# TranslationDir8Chan.net
KiCad netlist of a schematic drawn in Altium Designer
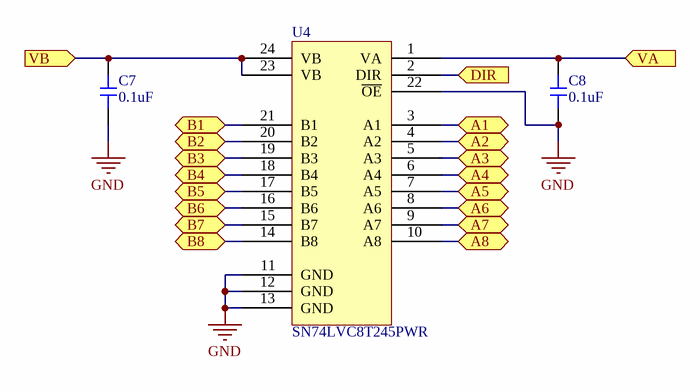
[diagram p0: TranslationDir8Chan.SchDoc]

(export (version "E")
  (design (tool "Eeschema 10.0.6"))
  (components
    (comp (ref "C7")
      (value "0.1uF")
      (footprint "AMDC:0603-CAP")
      (description "Capacitor")
      (libsource (lib "AMDC") (part "Capacitor"))
    )
    (comp (ref "C8")
      (value "0.1uF")
      (footprint "AMDC:0603-CAP")
      (description "Capacitor")
      (libsource (lib "AMDC") (part "Capacitor"))
    )
    (comp (ref "U4")
      (value "SN74LVC8T245PWR")
      (footprint "AMDC:TSOP65P640X120-24N")
      (description "IC BUS TRANSCVR 8BIT 24TSSOP")
      (libsource (lib "AMDC") (part "SN74LVC8T245PWR"))
    )
  )
  (nets
    (net (code "1") (name "/A1") (class "Default")
      (node (ref "U4") (pin "3") (pinfunction "A1_3") (pintype "passive"))
    )
    (net (code "2") (name "/A2") (class "Default")
      (node (ref "U4") (pin "4") (pinfunction "A2_4") (pintype "passive"))
    )
    (net (code "3") (name "/A3") (class "Default")
      (node (ref "U4") (pin "5") (pinfunction "A3_5") (pintype "passive"))
    )
    (net (code "4") (name "/A4") (class "Default")
      (node (ref "U4") (pin "6") (pinfunction "A4_6") (pintype "passive"))
    )
    (net (code "5") (name "/A5") (class "Default")
      (node (ref "U4") (pin "7") (pinfunction "A5_7") (pintype "passive"))
    )
    (net (code "6") (name "/A6") (class "Default")
      (node (ref "U4") (pin "8") (pinfunction "A6_8") (pintype "passive"))
    )
    (net (code "7") (name "/A7") (class "Default")
      (node (ref "U4") (pin "9") (pinfunction "A7_9") (pintype "passive"))
    )
    (net (code "8") (name "/A8") (class "Default")
      (node (ref "U4") (pin "10") (pinfunction "A8_10") (pintype "passive"))
    )
    (net (code "9") (name "/B1") (class "Default")
      (node (ref "U4") (pin "21") (pinfunction "B1_21") (pintype "passive"))
    )
    (net (code "10") (name "/B2") (class "Default")
      (node (ref "U4") (pin "20") (pinfunction "B2_20") (pintype "passive"))
    )
    (net (code "11") (name "/B3") (class "Default")
      (node (ref "U4") (pin "19") (pinfunction "B3_19") (pintype "passive"))
    )
    (net (code "12") (name "/B4") (class "Default")
      (node (ref "U4") (pin "18") (pinfunction "B4_18") (pintype "passive"))
    )
    (net (code "13") (name "/B5") (class "Default")
      (node (ref "U4") (pin "17") (pinfunction "B5_17") (pintype "passive"))
    )
    (net (code "14") (name "/B6") (class "Default")
      (node (ref "U4") (pin "16") (pinfunction "B6_16") (pintype "passive"))
    )
    (net (code "15") (name "/B7") (class "Default")
      (node (ref "U4") (pin "15") (pinfunction "B7_15") (pintype "passive"))
    )
    (net (code "16") (name "/B8") (class "Default")
      (node (ref "U4") (pin "14") (pinfunction "B8_14") (pintype "passive"))
    )
    (net (code "17") (name "/DIR") (class "Default")
      (node (ref "U4") (pin "2") (pinfunction "DIR_2") (pintype "passive"))
    )
    (net (code "18") (name "/VA") (class "Default")
      (node (ref "C8") (pin "1") (pinfunction "1_1") (pintype "passive"))
      (node (ref "U4") (pin "1") (pinfunction "VA_1") (pintype "passive"))
    )
    (net (code "19") (name "/VB") (class "Default")
      (node (ref "C7") (pin "1") (pinfunction "1_1") (pintype "passive"))
      (node (ref "U4") (pin "23") (pinfunction "VB_23") (pintype "passive"))
      (node (ref "U4") (pin "24") (pinfunction "VB_24") (pintype "passive"))
    )
    (net (code "20") (name "GND") (class "Default")
      (node (ref "C7") (pin "2") (pinfunction "2_2") (pintype "passive"))
      (node (ref "C8") (pin "2") (pinfunction "2_2") (pintype "passive"))
      (node (ref "U4") (pin "11") (pinfunction "GND_11") (pintype "passive"))
      (node (ref "U4") (pin "12") (pinfunction "GND_12") (pintype "passive"))
      (node (ref "U4") (pin "13") (pinfunction "GND_13") (pintype "passive"))
      (node (ref "U4") (pin "22") (pinfunction "~{OE}_22") (pintype "passive"))
    )
  )
)
